# button_board.net
KiCad netlist of a schematic drawn in EAGLE
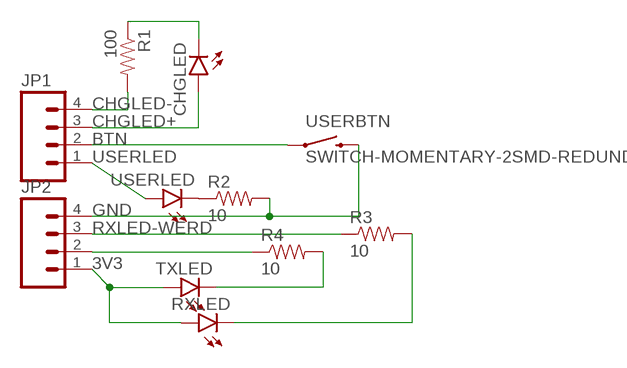
[diagram p0: schematic, sheet 1]

(export (version "E")
  (design (tool "Eeschema 10.0.6"))
  (components
    (comp (ref "CHGLED")
      (value "LED-FKIT-1206")
      (footprint "eagle-import:FKIT-LED-1206")
      (libsource (lib "eagle-import") (part "LED-FKIT-1206"))
    )
    (comp (ref "JP1")
      (value "M04PTH")
      (footprint "eagle-import:1X04")
      (libsource (lib "eagle-import") (part "M04PTH"))
    )
    (comp (ref "JP2")
      (value "M04PTH")
      (footprint "eagle-import:1X04")
      (libsource (lib "eagle-import") (part "M04PTH"))
    )
    (comp (ref "R1")
      (value "100")
      (footprint "eagle-import:0603-RES")
      (libsource (lib "eagle-import") (part "RESISTOR0603-RES"))
    )
    (comp (ref "R2")
      (value "10")
      (footprint "eagle-import:0603-RES")
      (libsource (lib "eagle-import") (part "RESISTOR0603-RES"))
    )
    (comp (ref "R3")
      (value "10")
      (footprint "eagle-import:0603-RES")
      (libsource (lib "eagle-import") (part "RESISTOR0603-RES"))
    )
    (comp (ref "R4")
      (value "10")
      (footprint "eagle-import:0603-RES")
      (libsource (lib "eagle-import") (part "RESISTOR0603-RES"))
    )
    (comp (ref "RXLED")
      (value "LED-FKIT-1206")
      (footprint "eagle-import:FKIT-LED-1206")
      (libsource (lib "eagle-import") (part "LED-FKIT-1206"))
    )
    (comp (ref "TXLED")
      (value "LED-FKIT-1206")
      (footprint "eagle-import:FKIT-LED-1206")
      (libsource (lib "eagle-import") (part "LED-FKIT-1206"))
    )
    (comp (ref "USERBTN")
      (value "SWITCH-MOMENTARY-2SMD-REDUNDANT")
      (footprint "eagle-import:TACTILE-SWITCH-SMD")
      (libsource (lib "eagle-import") (part "SWITCH-MOMENTARY-2SMD-REDUNDANT"))
    )
    (comp (ref "USERLED")
      (value "LED-FKIT-1206")
      (footprint "eagle-import:FKIT-LED-1206")
      (libsource (lib "eagle-import") (part "LED-FKIT-1206"))
    )
  )
  (nets
    (net (code "1") (name "/3V3") (class "Default")
      (node (ref "JP2") (pin "1") (pinfunction "1_1") (pintype "passive"))
      (node (ref "RXLED") (pin "A") (pinfunction "A_A") (pintype "passive"))
      (node (ref "TXLED") (pin "A") (pinfunction "A_A") (pintype "passive"))
    )
    (net (code "2") (name "/BTN") (class "Default")
      (node (ref "JP1") (pin "2") (pinfunction "2_2") (pintype "passive"))
      (node (ref "USERBTN") (pin "1") (pinfunction "1_1") (pintype "passive"))
      (node (ref "USERBTN") (pin "2") (pinfunction "1_2") (pintype "passive"))
    )
    (net (code "3") (name "/CHGLED+") (class "Default")
      (node (ref "CHGLED") (pin "A") (pinfunction "A_A") (pintype "passive"))
      (node (ref "JP1") (pin "3") (pinfunction "3_3") (pintype "passive"))
    )
    (net (code "4") (name "/CHGLED-") (class "Default")
      (node (ref "JP1") (pin "4") (pinfunction "4_4") (pintype "passive"))
      (node (ref "R1") (pin "2") (pinfunction "2_2") (pintype "passive"))
    )
    (net (code "5") (name "/GND") (class "Default")
      (node (ref "JP2") (pin "4") (pinfunction "4_4") (pintype "passive"))
      (node (ref "R2") (pin "2") (pinfunction "2_2") (pintype "passive"))
      (node (ref "USERBTN") (pin "3") (pinfunction "2_3") (pintype "passive"))
      (node (ref "USERBTN") (pin "4") (pinfunction "2_4") (pintype "passive"))
    )
    (net (code "6") (name "/RXLED-WERD") (class "Default")
      (node (ref "R3") (pin "2") (pinfunction "2_2") (pintype "passive"))
      (node (ref "RXLED") (pin "C") (pinfunction "C_C") (pintype "passive"))
    )
    (net (code "7") (name "/USERLED") (class "Default")
      (node (ref "JP1") (pin "1") (pinfunction "1_1") (pintype "passive"))
      (node (ref "USERLED") (pin "A") (pinfunction "A_A") (pintype "passive"))
    )
    (net (code "8") (name "Net-(CHGLED-PadC)") (class "Default")
      (node (ref "CHGLED") (pin "C") (pinfunction "C_C") (pintype "passive"))
      (node (ref "R1") (pin "1") (pinfunction "1_1") (pintype "passive"))
    )
    (net (code "9") (name "Net-(JP2-Pad2)") (class "Default")
      (node (ref "JP2") (pin "2") (pinfunction "2_2") (pintype "passive"))
      (node (ref "R4") (pin "1") (pinfunction "1_1") (pintype "passive"))
    )
    (net (code "10") (name "Net-(JP2-Pad3)") (class "Default")
      (node (ref "JP2") (pin "3") (pinfunction "3_3") (pintype "passive"))
      (node (ref "R3") (pin "1") (pinfunction "1_1") (pintype "passive"))
    )
    (net (code "11") (name "Net-(R2-Pad1)") (class "Default")
      (node (ref "R2") (pin "1") (pinfunction "1_1") (pintype "passive"))
      (node (ref "USERLED") (pin "C") (pinfunction "C_C") (pintype "passive"))
    )
    (net (code "12") (name "Net-(R4-Pad2)") (class "Default")
      (node (ref "R4") (pin "2") (pinfunction "2_2") (pintype "passive"))
      (node (ref "TXLED") (pin "C") (pinfunction "C_C") (pintype "passive"))
    )
  )
)
